# 01_-_TOP_VIEW.net
KiCad netlist of a schematic drawn in Altium Designer
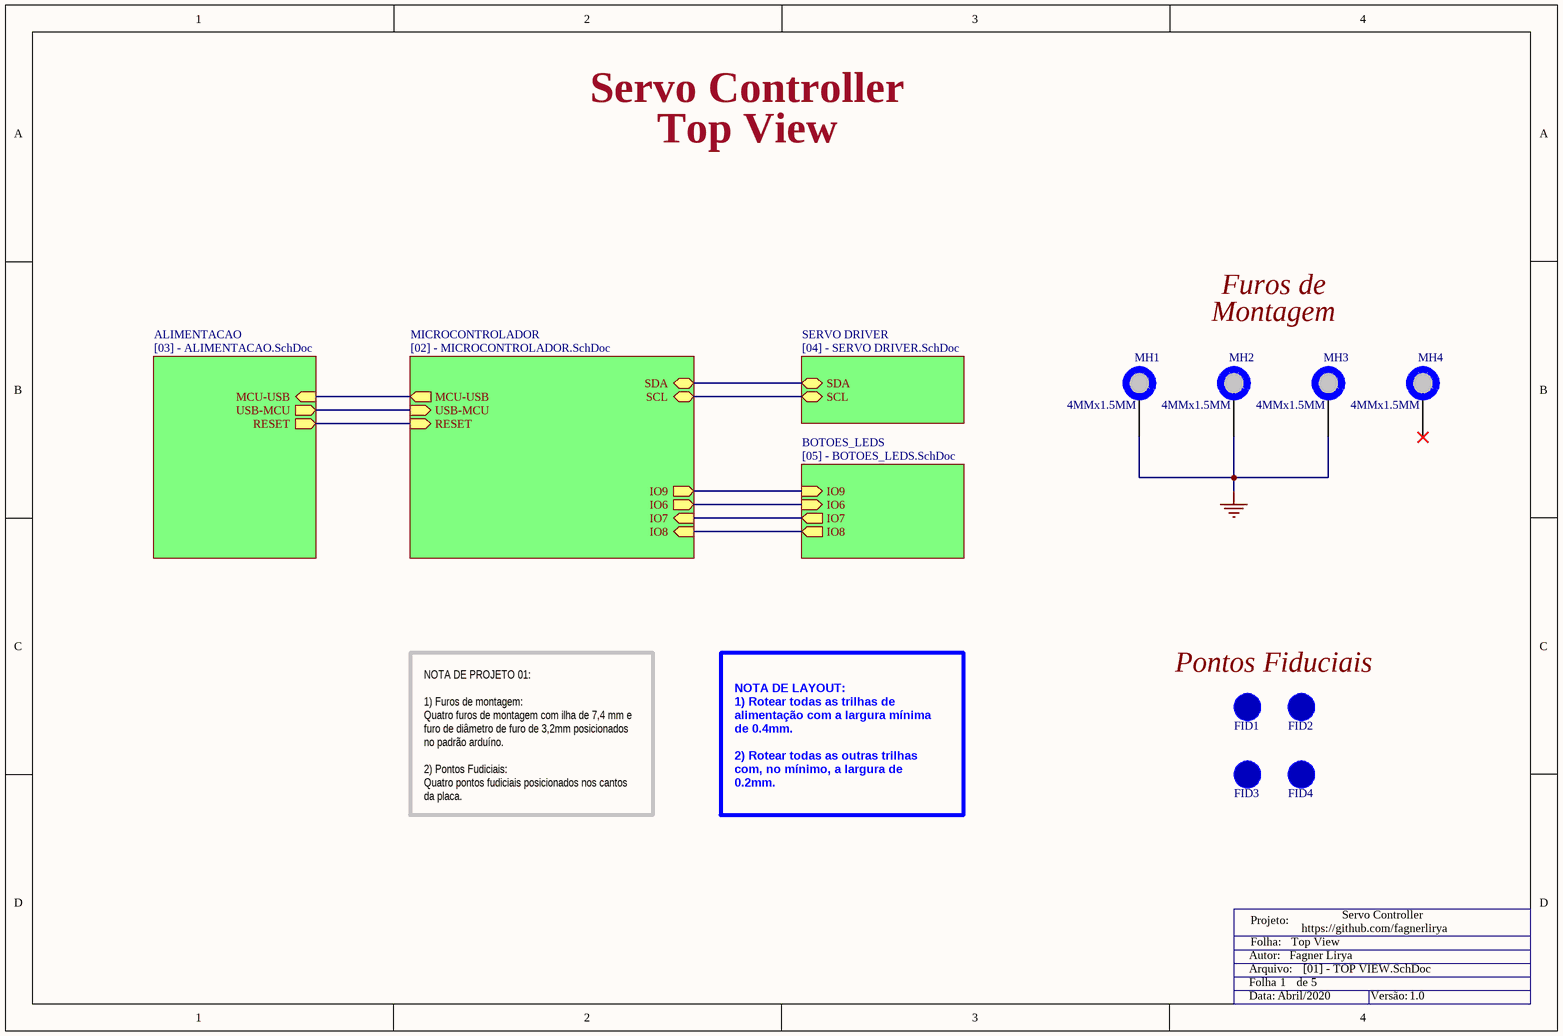
[diagram p0: [01] - TOP VIEW.SchDoc]

(export (version "E")
  (design (tool "Eeschema 10.0.6"))
  (components
    (comp (ref "FID1")
      (value "FID_1MMC")
      (footprint "FID_40X120D")
      (description "Fiducial 40mil Diameter, 120mil Mask")
      (libsource (lib "Servo_Control_Lib") (part "FID_1MMC"))
    )
    (comp (ref "FID2")
      (value "FID_1MMC")
      (footprint "FID_40X120D")
      (description "Fiducial 40mil Diameter, 120mil Mask")
      (libsource (lib "Servo_Control_Lib") (part "FID_1MMC"))
    )
    (comp (ref "FID3")
      (value "FID_1MMC")
      (footprint "FID_40X120D")
      (description "Fiducial 40mil Diameter, 120mil Mask")
      (libsource (lib "Servo_Control_Lib") (part "FID_1MMC"))
    )
    (comp (ref "FID4")
      (value "FID_1MMC")
      (footprint "FID_40X120D")
      (description "Fiducial 40mil Diameter, 120mil Mask")
      (libsource (lib "Servo_Control_Lib") (part "FID_1MMC"))
    )
    (comp (ref "MH1")
      (value "4MMx1.5MM")
      (footprint "MH_7.4MMD_3.2MMD")
      (description "Pad with a hole 4mm x 1.5mm")
      (libsource (lib "Servo_Control_Lib") (part "PAD_WITH_HOLE_4MMx1.5MM"))
    )
    (comp (ref "MH2")
      (value "4MMx1.5MM")
      (footprint "MH_7.4MMD_3.2MMD")
      (description "Pad with a hole 4mm x 1.5mm")
      (libsource (lib "Servo_Control_Lib") (part "PAD_WITH_HOLE_4MMx1.5MM"))
    )
    (comp (ref "MH3")
      (value "4MMx1.5MM")
      (footprint "MH_7.4MMD_3.2MMD")
      (description "Pad with a hole 4mm x 1.5mm")
      (libsource (lib "Servo_Control_Lib") (part "PAD_WITH_HOLE_4MMx1.5MM"))
    )
    (comp (ref "MH4")
      (value "4MMx1.5MM")
      (footprint "MH_7.4MMD_3.2MMD_NON_COPPER_NPTH")
      (description "Pad with a hole 4mm x 1.5mm")
      (libsource (lib "Servo_Control_Lib") (part "PAD_WITH_HOLE_4MMx1.5MM"))
    )
    (comp (ref "TitleBlock1")
      (value "Title Block")
      (libsource (lib "Servo_Control_Lib") (part "Title Block"))
    )
  )
  (nets
    (net (code "10") (name "GND") (class "Default")
      (node (ref "MH1") (pin "1") (pinfunction "1_1") (pintype "passive"))
      (node (ref "MH2") (pin "1") (pinfunction "1_1") (pintype "passive"))
      (node (ref "MH3") (pin "1") (pinfunction "1_1") (pintype "passive"))
    )
    (net (code "11") (name "unconnected-(MH4-Pad1)") (class "Default")
      (node (ref "MH4") (pin "1") (pinfunction "1_1") (pintype "passive+no_connect"))
    )
  )
)
